# OTR.net
KiCad netlist of a schematic drawn in EAGLE
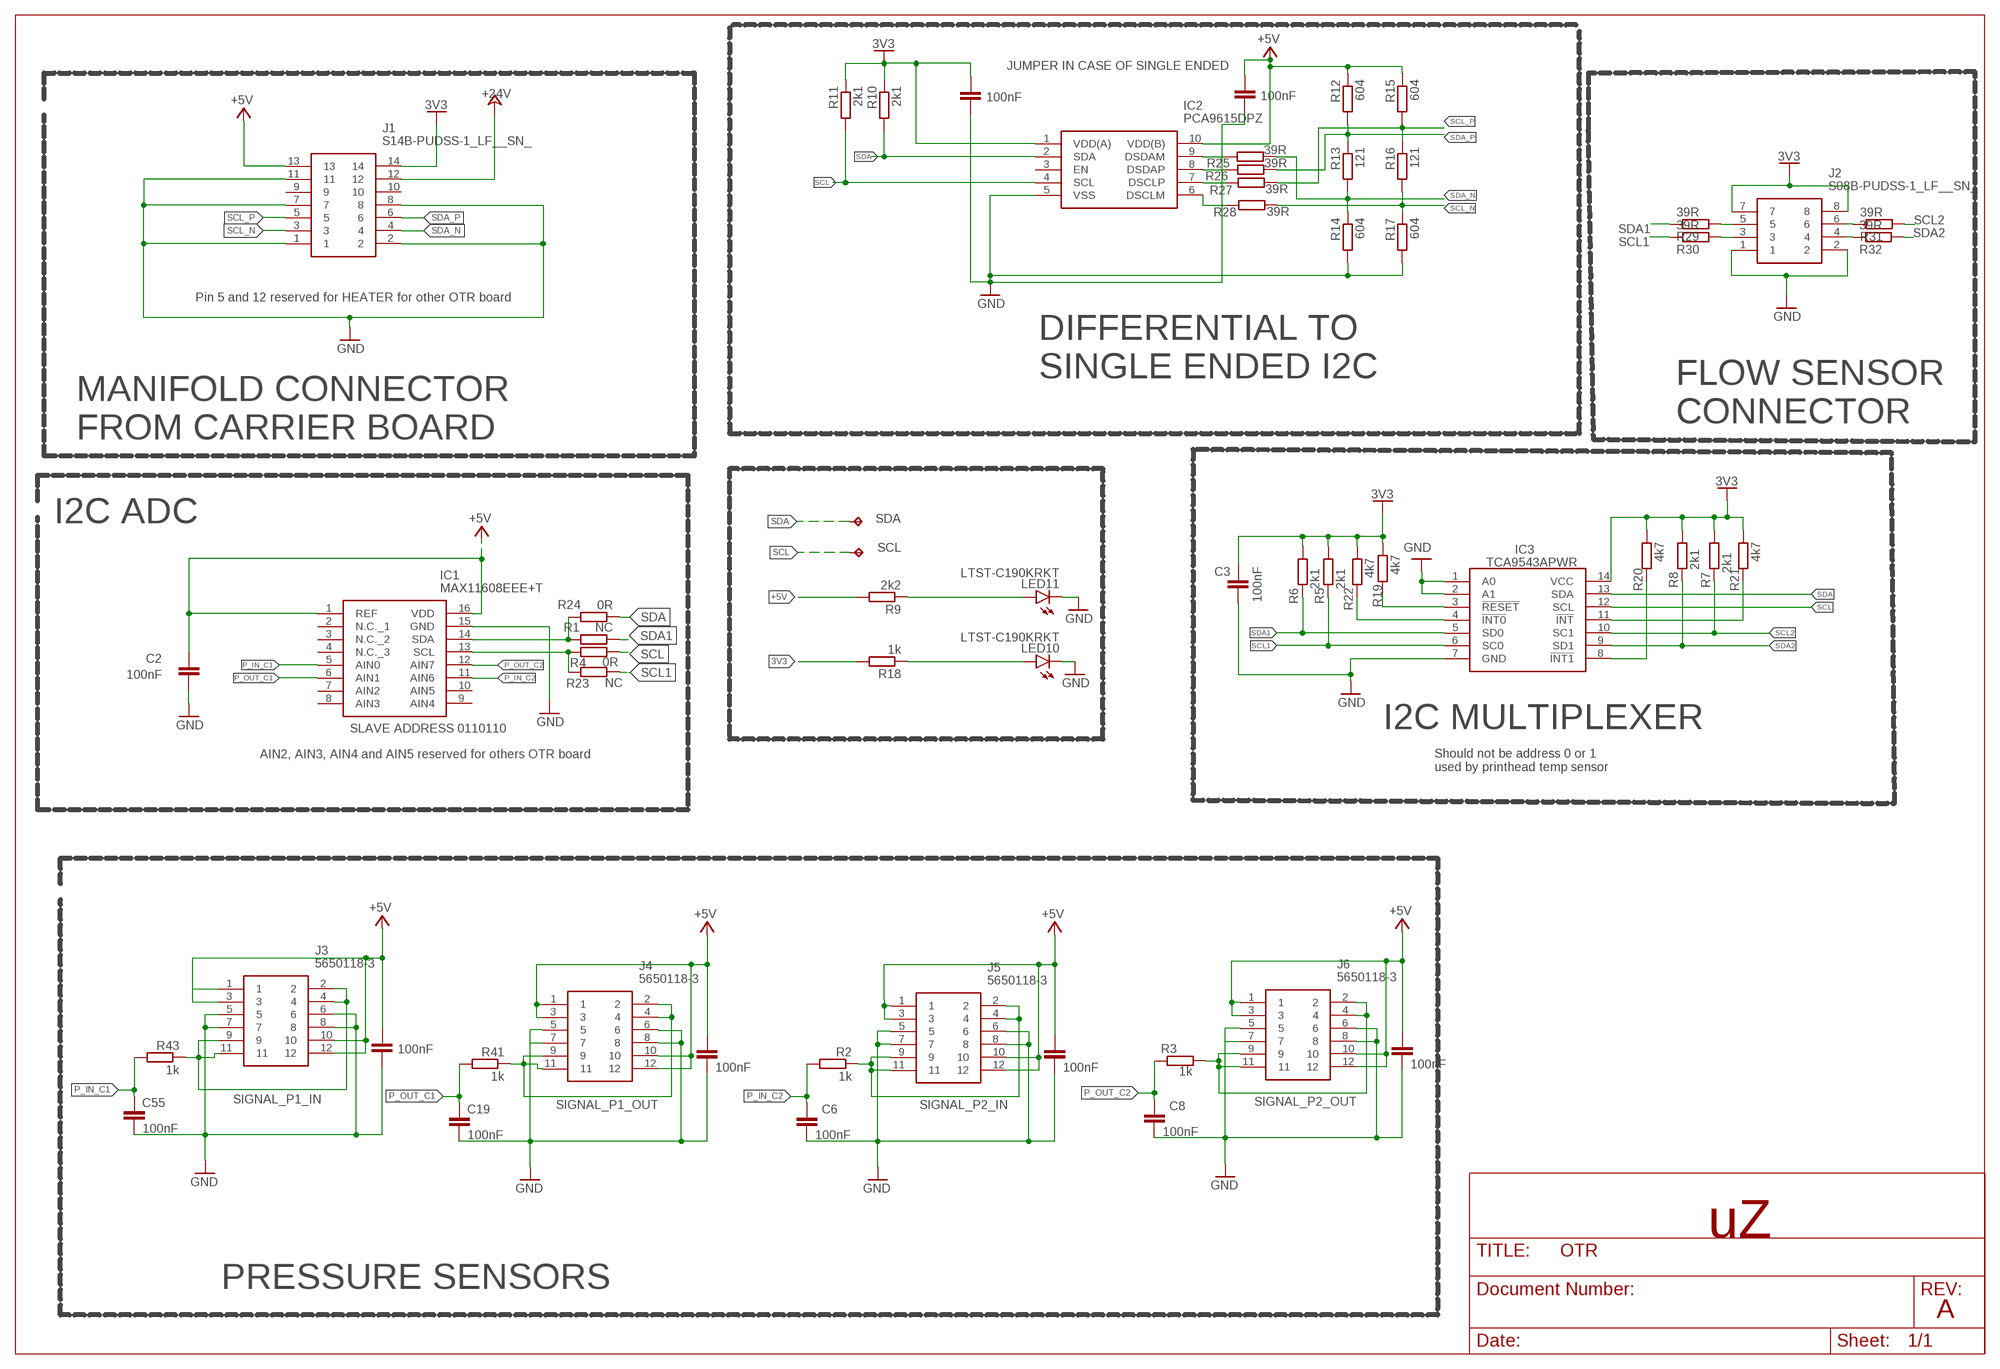
[diagram p0: schematic, sheet 1]

(export (version "E")
  (design (tool "Eeschema 10.0.6"))
  (components
    (comp (ref "C1")
      (value "100nF")
      (footprint "eagle-import:C0603")
      (libsource (lib "eagle-import") (part "C-EUC0603"))
    )
    (comp (ref "C2")
      (value "100nF")
      (footprint "eagle-import:C0603")
      (libsource (lib "eagle-import") (part "C-EUC0603"))
    )
    (comp (ref "C3")
      (value "100nF")
      (footprint "eagle-import:C0603")
      (libsource (lib "eagle-import") (part "C-EUC0603"))
    )
    (comp (ref "C4")
      (value "100nF")
      (footprint "eagle-import:C0603")
      (libsource (lib "eagle-import") (part "C-EUC0603"))
    )
    (comp (ref "C5")
      (value "100nF")
      (footprint "eagle-import:C0603")
      (libsource (lib "eagle-import") (part "C-EUC0603"))
    )
    (comp (ref "C6")
      (value "100nF")
      (footprint "eagle-import:C0603")
      (libsource (lib "eagle-import") (part "C-EUC0603"))
    )
    (comp (ref "C7")
      (value "100nF")
      (footprint "eagle-import:C0603")
      (libsource (lib "eagle-import") (part "C-EUC0603"))
    )
    (comp (ref "C8")
      (value "100nF")
      (footprint "eagle-import:C0603")
      (libsource (lib "eagle-import") (part "C-EUC0603"))
    )
    (comp (ref "C16")
      (value "100nF")
      (footprint "eagle-import:C0603")
      (libsource (lib "eagle-import") (part "C-EUC0603"))
    )
    (comp (ref "C19")
      (value "100nF")
      (footprint "eagle-import:C0603")
      (libsource (lib "eagle-import") (part "C-EUC0603"))
    )
    (comp (ref "C24")
      (value "100nF")
      (footprint "eagle-import:C0603")
      (libsource (lib "eagle-import") (part "C-EUC0603"))
    )
    (comp (ref "C55")
      (value "100nF")
      (footprint "eagle-import:C0603")
      (libsource (lib "eagle-import") (part "C-EUC0603"))
    )
    (comp (ref "IC1")
      (value "MAX11608EEE+T")
      (footprint "eagle-import:SOP64P602X175-16N")
      (fields (field (name "MOUSER_PART_NUMBER") "700-MAX11608EEE+T"))
      (libsource (lib "eagle-import") (part "MAX11608EEE+T"))
    )
    (comp (ref "IC2")
      (value "PCA9615DPZ")
      (footprint "eagle-import:SOP50P490X110-10N")
      (fields (field (name "MOUSER_PART_NUMBER") "771-PCA9615DPZ"))
      (libsource (lib "eagle-import") (part "PCA9615DPZ"))
    )
    (comp (ref "IC3")
      (value "TCA9543APWR")
      (footprint "eagle-import:SOP65P640X120-14N")
      (fields (field (name "MOUSER_PART_NUMBER") "595-TCA9543APWR"))
      (libsource (lib "eagle-import") (part "TCA9543APWR"))
    )
    (comp (ref "J1")
      (value "S14B-PUDSS-1_LF__SN_")
      (footprint "eagle-import:S14BPUDSS1LFSN")
      (fields (field (name "MANUFACTURER_PART_NUMBER") "S14B-PUDSS-1(LF)(SN)"))
      (libsource (lib "eagle-import") (part "S14B-PUDSS-1_LF__SN_"))
    )
    (comp (ref "J2")
      (value "S08B-PUDSS-1_LF__SN_")
      (footprint "eagle-import:S08B-PUDSS-1_LF__SN_")
      (fields (field (name "MANUFACTURER_PART_NUMBER") "S14B-PUDSS-1(LF)(SN)"))
      (libsource (lib "eagle-import") (part "S08B-PUDSS-1_LF__SN_"))
    )
    (comp (ref "J3")
      (value "5650118-3")
      (footprint "eagle-import:56501183")
      (fields (field (name "MOUSER_PART_NUMBER") "571-5650118-3"))
      (libsource (lib "eagle-import") (part "5650118-3"))
    )
    (comp (ref "J4")
      (value "5650118-3")
      (footprint "eagle-import:56501183")
      (fields (field (name "MOUSER_PART_NUMBER") "571-5650118-3"))
      (libsource (lib "eagle-import") (part "5650118-3"))
    )
    (comp (ref "J5")
      (value "5650118-3")
      (footprint "eagle-import:56501183")
      (fields (field (name "MOUSER_PART_NUMBER") "571-5650118-3"))
      (libsource (lib "eagle-import") (part "5650118-3"))
    )
    (comp (ref "J6")
      (value "5650118-3")
      (footprint "eagle-import:56501183")
      (fields (field (name "MOUSER_PART_NUMBER") "571-5650118-3"))
      (libsource (lib "eagle-import") (part "5650118-3"))
    )
    (comp (ref "LED10")
      (value "LTST-C190KRKT")
      (footprint "eagle-import:CHIPLED_0603")
      (libsource (lib "eagle-import") (part "LEDCHIPLED_0603"))
    )
    (comp (ref "LED11")
      (value "LTST-C190KRKT")
      (footprint "eagle-import:CHIPLED_0603")
      (libsource (lib "eagle-import") (part "LEDCHIPLED_0603"))
    )
    (comp (ref "R1")
      (value "NC")
      (footprint "eagle-import:R0603")
      (libsource (lib "eagle-import") (part "R-EU_R0603"))
    )
    (comp (ref "R2")
      (value "1k")
      (footprint "eagle-import:R0603")
      (libsource (lib "eagle-import") (part "R-EU_R0603"))
    )
    (comp (ref "R3")
      (value "1k")
      (footprint "eagle-import:R0603")
      (libsource (lib "eagle-import") (part "R-EU_R0603"))
    )
    (comp (ref "R4")
      (value "0R")
      (footprint "eagle-import:R0603")
      (libsource (lib "eagle-import") (part "R-EU_R0603"))
    )
    (comp (ref "R5")
      (value "2k1")
      (footprint "eagle-import:R0603")
      (libsource (lib "eagle-import") (part "R-EU_R0603"))
    )
    (comp (ref "R6")
      (value "2k1")
      (footprint "eagle-import:R0603")
      (libsource (lib "eagle-import") (part "R-EU_R0603"))
    )
    (comp (ref "R7")
      (value "2k1")
      (footprint "eagle-import:R0603")
      (libsource (lib "eagle-import") (part "R-EU_R0603"))
    )
    (comp (ref "R8")
      (value "2k1")
      (footprint "eagle-import:R0603")
      (libsource (lib "eagle-import") (part "R-EU_R0603"))
    )
    (comp (ref "R9")
      (value "2k2")
      (footprint "eagle-import:R0603")
      (libsource (lib "eagle-import") (part "R-EU_R0603"))
    )
    (comp (ref "R10")
      (value "2k1")
      (footprint "eagle-import:R0603")
      (libsource (lib "eagle-import") (part "R-EU_R0603"))
    )
    (comp (ref "R11")
      (value "2k1")
      (footprint "eagle-import:R0603")
      (libsource (lib "eagle-import") (part "R-EU_R0603"))
    )
    (comp (ref "R12")
      (value "604")
      (footprint "eagle-import:R0603")
      (libsource (lib "eagle-import") (part "R-EU_R0603"))
    )
    (comp (ref "R13")
      (value "121")
      (footprint "eagle-import:R0603")
      (libsource (lib "eagle-import") (part "R-EU_R0603"))
    )
    (comp (ref "R14")
      (value "604")
      (footprint "eagle-import:R0603")
      (libsource (lib "eagle-import") (part "R-EU_R0603"))
    )
    (comp (ref "R15")
      (value "604")
      (footprint "eagle-import:R0603")
      (libsource (lib "eagle-import") (part "R-EU_R0603"))
    )
    (comp (ref "R16")
      (value "121")
      (footprint "eagle-import:R0603")
      (libsource (lib "eagle-import") (part "R-EU_R0603"))
    )
    (comp (ref "R17")
      (value "604")
      (footprint "eagle-import:R0603")
      (libsource (lib "eagle-import") (part "R-EU_R0603"))
    )
    (comp (ref "R18")
      (value "1k")
      (footprint "eagle-import:R0603")
      (libsource (lib "eagle-import") (part "R-EU_R0603"))
    )
    (comp (ref "R19")
      (value "4k7")
      (footprint "eagle-import:R0603")
      (libsource (lib "eagle-import") (part "R-EU_R0603"))
    )
    (comp (ref "R20")
      (value "4k7")
      (footprint "eagle-import:R0603")
      (libsource (lib "eagle-import") (part "R-EU_R0603"))
    )
    (comp (ref "R21")
      (value "4k7")
      (footprint "eagle-import:R0603")
      (libsource (lib "eagle-import") (part "R-EU_R0603"))
    )
    (comp (ref "R22")
      (value "4k7")
      (footprint "eagle-import:R0603")
      (libsource (lib "eagle-import") (part "R-EU_R0603"))
    )
    (comp (ref "R23")
      (value "NC")
      (footprint "eagle-import:R0603")
      (libsource (lib "eagle-import") (part "R-EU_R0603"))
    )
    (comp (ref "R24")
      (value "0R")
      (footprint "eagle-import:R0603")
      (libsource (lib "eagle-import") (part "R-EU_R0603"))
    )
    (comp (ref "R25")
      (value "39R")
      (footprint "eagle-import:R0603")
      (libsource (lib "eagle-import") (part "R-EU_R0603"))
    )
    (comp (ref "R26")
      (value "39R")
      (footprint "eagle-import:R0603")
      (libsource (lib "eagle-import") (part "R-EU_R0603"))
    )
    (comp (ref "R27")
      (value "39R")
      (footprint "eagle-import:R0603")
      (libsource (lib "eagle-import") (part "R-EU_R0603"))
    )
    (comp (ref "R28")
      (value "39R")
      (footprint "eagle-import:R0603")
      (libsource (lib "eagle-import") (part "R-EU_R0603"))
    )
    (comp (ref "R29")
      (value "39R")
      (footprint "eagle-import:R0603")
      (libsource (lib "eagle-import") (part "R-EU_R0603"))
    )
    (comp (ref "R30")
      (value "39R")
      (footprint "eagle-import:R0603")
      (libsource (lib "eagle-import") (part "R-EU_R0603"))
    )
    (comp (ref "R31")
      (value "39R")
      (footprint "eagle-import:R0603")
      (libsource (lib "eagle-import") (part "R-EU_R0603"))
    )
    (comp (ref "R32")
      (value "39R")
      (footprint "eagle-import:R0603")
      (libsource (lib "eagle-import") (part "R-EU_R0603"))
    )
    (comp (ref "R41")
      (value "1k")
      (footprint "eagle-import:R0603")
      (libsource (lib "eagle-import") (part "R-EU_R0603"))
    )
    (comp (ref "R43")
      (value "1k")
      (footprint "eagle-import:R0603")
      (libsource (lib "eagle-import") (part "R-EU_R0603"))
    )
    (comp (ref "SCL")
      (value "TEST_POINT")
      (footprint "eagle-import:TEST_POINT")
      (libsource (lib "eagle-import") (part "TEST_POINT"))
    )
    (comp (ref "SDA")
      (value "TEST_POINT")
      (footprint "eagle-import:TEST_POINT")
      (libsource (lib "eagle-import") (part "TEST_POINT"))
    )
  )
  (nets
    (net (code "1") (name "+5V") (class "Default")
      (node (ref "C16") (pin "1") (pinfunction "1_1") (pintype "passive"))
      (node (ref "C2") (pin "1") (pinfunction "1_1") (pintype "passive"))
      (node (ref "C24") (pin "1") (pinfunction "1_1") (pintype "passive"))
      (node (ref "C4") (pin "1") (pinfunction "1_1") (pintype "passive"))
      (node (ref "C5") (pin "1") (pinfunction "1_1") (pintype "passive"))
      (node (ref "C7") (pin "1") (pinfunction "1_1") (pintype "passive"))
      (node (ref "IC1") (pin "1") (pinfunction "REF_1") (pintype "bidirectional"))
      (node (ref "IC1") (pin "16") (pinfunction "VDD_16") (pintype "bidirectional"))
      (node (ref "IC2") (pin "10") (pinfunction "VDD(B)_10") (pintype "bidirectional"))
      (node (ref "J1") (pin "13") (pinfunction "13_13") (pintype "bidirectional"))
      (node (ref "J3") (pin "1") (pinfunction "1_1") (pintype "bidirectional"))
      (node (ref "J3") (pin "10") (pinfunction "10_10") (pintype "bidirectional"))
      (node (ref "J3") (pin "12") (pinfunction "12_12") (pintype "bidirectional"))
      (node (ref "J3") (pin "3") (pinfunction "3_3") (pintype "bidirectional"))
      (node (ref "J4") (pin "1") (pinfunction "1_1") (pintype "bidirectional"))
      (node (ref "J4") (pin "10") (pinfunction "10_10") (pintype "bidirectional"))
      (node (ref "J4") (pin "12") (pinfunction "12_12") (pintype "bidirectional"))
      (node (ref "J4") (pin "3") (pinfunction "3_3") (pintype "bidirectional"))
      (node (ref "J5") (pin "1") (pinfunction "1_1") (pintype "bidirectional"))
      (node (ref "J5") (pin "10") (pinfunction "10_10") (pintype "bidirectional"))
      (node (ref "J5") (pin "12") (pinfunction "12_12") (pintype "bidirectional"))
      (node (ref "J5") (pin "3") (pinfunction "3_3") (pintype "bidirectional"))
      (node (ref "J6") (pin "1") (pinfunction "1_1") (pintype "bidirectional"))
      (node (ref "J6") (pin "10") (pinfunction "10_10") (pintype "bidirectional"))
      (node (ref "J6") (pin "12") (pinfunction "12_12") (pintype "bidirectional"))
      (node (ref "J6") (pin "3") (pinfunction "3_3") (pintype "bidirectional"))
      (node (ref "R12") (pin "1") (pinfunction "1_1") (pintype "passive"))
      (node (ref "R15") (pin "1") (pinfunction "1_1") (pintype "passive"))
      (node (ref "R9") (pin "2") (pinfunction "2_2") (pintype "passive"))
    )
    (net (code "2") (name "+24V") (class "Default")
      (node (ref "J1") (pin "12") (pinfunction "12_12") (pintype "bidirectional"))
    )
    (net (code "3") (name "/SIGNAL_P1_IN") (class "Default")
      (node (ref "J3") (pin "11") (pinfunction "11_11") (pintype "bidirectional"))
      (node (ref "J3") (pin "2") (pinfunction "2_2") (pintype "bidirectional"))
      (node (ref "J3") (pin "4") (pinfunction "4_4") (pintype "bidirectional"))
      (node (ref "J3") (pin "9") (pinfunction "9_9") (pintype "bidirectional"))
      (node (ref "R43") (pin "1") (pinfunction "1_1") (pintype "passive"))
    )
    (net (code "4") (name "/SIGNAL_P1_OUT") (class "Default")
      (node (ref "J4") (pin "11") (pinfunction "11_11") (pintype "bidirectional"))
      (node (ref "J4") (pin "2") (pinfunction "2_2") (pintype "bidirectional"))
      (node (ref "J4") (pin "4") (pinfunction "4_4") (pintype "bidirectional"))
      (node (ref "J4") (pin "9") (pinfunction "9_9") (pintype "bidirectional"))
      (node (ref "R41") (pin "1") (pinfunction "1_1") (pintype "passive"))
    )
    (net (code "5") (name "/SIGNAL_P2_IN") (class "Default")
      (node (ref "J5") (pin "11") (pinfunction "11_11") (pintype "bidirectional"))
      (node (ref "J5") (pin "2") (pinfunction "2_2") (pintype "bidirectional"))
      (node (ref "J5") (pin "4") (pinfunction "4_4") (pintype "bidirectional"))
      (node (ref "J5") (pin "9") (pinfunction "9_9") (pintype "bidirectional"))
      (node (ref "R2") (pin "1") (pinfunction "1_1") (pintype "passive"))
    )
    (net (code "6") (name "/SIGNAL_P2_OUT") (class "Default")
      (node (ref "J6") (pin "11") (pinfunction "11_11") (pintype "bidirectional"))
      (node (ref "J6") (pin "2") (pinfunction "2_2") (pintype "bidirectional"))
      (node (ref "J6") (pin "4") (pinfunction "4_4") (pintype "bidirectional"))
      (node (ref "J6") (pin "9") (pinfunction "9_9") (pintype "bidirectional"))
      (node (ref "R3") (pin "1") (pinfunction "1_1") (pintype "passive"))
    )
    (net (code "7") (name "3V3") (class "Default")
      (node (ref "C1") (pin "1") (pinfunction "1_1") (pintype "passive"))
      (node (ref "C3") (pin "2") (pinfunction "2_2") (pintype "passive"))
      (node (ref "IC2") (pin "1") (pinfunction "VDD(A)_1") (pintype "bidirectional"))
      (node (ref "IC3") (pin "14") (pinfunction "VCC_14") (pintype "bidirectional"))
      (node (ref "J1") (pin "14") (pinfunction "14_14") (pintype "bidirectional"))
      (node (ref "J2") (pin "7") (pinfunction "7_7") (pintype "bidirectional"))
      (node (ref "J2") (pin "8") (pinfunction "8_8") (pintype "bidirectional"))
      (node (ref "R10") (pin "1") (pinfunction "1_1") (pintype "passive"))
      (node (ref "R11") (pin "1") (pinfunction "1_1") (pintype "passive"))
      (node (ref "R18") (pin "2") (pinfunction "2_2") (pintype "passive"))
      (node (ref "R19") (pin "2") (pinfunction "2_2") (pintype "passive"))
      (node (ref "R20") (pin "2") (pinfunction "2_2") (pintype "passive"))
      (node (ref "R21") (pin "2") (pinfunction "2_2") (pintype "passive"))
      (node (ref "R22") (pin "2") (pinfunction "2_2") (pintype "passive"))
      (node (ref "R5") (pin "1") (pinfunction "1_1") (pintype "passive"))
      (node (ref "R6") (pin "1") (pinfunction "1_1") (pintype "passive"))
      (node (ref "R7") (pin "1") (pinfunction "1_1") (pintype "passive"))
      (node (ref "R8") (pin "1") (pinfunction "1_1") (pintype "passive"))
    )
    (net (code "8") (name "GND") (class "Default")
      (node (ref "C1") (pin "2") (pinfunction "2_2") (pintype "passive"))
      (node (ref "C16") (pin "2") (pinfunction "2_2") (pintype "passive"))
      (node (ref "C19") (pin "2") (pinfunction "2_2") (pintype "passive"))
      (node (ref "C2") (pin "2") (pinfunction "2_2") (pintype "passive"))
      (node (ref "C24") (pin "2") (pinfunction "2_2") (pintype "passive"))
      (node (ref "C3") (pin "1") (pinfunction "1_1") (pintype "passive"))
      (node (ref "C4") (pin "2") (pinfunction "2_2") (pintype "passive"))
      (node (ref "C5") (pin "2") (pinfunction "2_2") (pintype "passive"))
      (node (ref "C55") (pin "2") (pinfunction "2_2") (pintype "passive"))
      (node (ref "C6") (pin "2") (pinfunction "2_2") (pintype "passive"))
      (node (ref "C7") (pin "2") (pinfunction "2_2") (pintype "passive"))
      (node (ref "C8") (pin "2") (pinfunction "2_2") (pintype "passive"))
      (node (ref "IC1") (pin "15") (pinfunction "GND_15") (pintype "bidirectional"))
      (node (ref "IC2") (pin "5") (pinfunction "VSS_5") (pintype "bidirectional"))
      (node (ref "IC3") (pin "1") (pinfunction "A0_1") (pintype "bidirectional"))
      (node (ref "IC3") (pin "2") (pinfunction "A1_2") (pintype "bidirectional"))
      (node (ref "IC3") (pin "7") (pinfunction "GND_7") (pintype "bidirectional"))
      (node (ref "J1") (pin "1") (pinfunction "1_1") (pintype "bidirectional"))
      (node (ref "J1") (pin "11") (pinfunction "11_11") (pintype "bidirectional"))
      (node (ref "J1") (pin "2") (pinfunction "2_2") (pintype "bidirectional"))
      (node (ref "J1") (pin "7") (pinfunction "7_7") (pintype "bidirectional"))
      (node (ref "J1") (pin "8") (pinfunction "8_8") (pintype "bidirectional"))
      (node (ref "J2") (pin "1") (pinfunction "1_1") (pintype "bidirectional"))
      (node (ref "J2") (pin "2") (pinfunction "2_2") (pintype "bidirectional"))
      (node (ref "J3") (pin "5") (pinfunction "5_5") (pintype "bidirectional"))
      (node (ref "J3") (pin "6") (pinfunction "6_6") (pintype "bidirectional"))
      (node (ref "J3") (pin "7") (pinfunction "7_7") (pintype "bidirectional"))
      (node (ref "J3") (pin "8") (pinfunction "8_8") (pintype "bidirectional"))
      (node (ref "J4") (pin "5") (pinfunction "5_5") (pintype "bidirectional"))
      (node (ref "J4") (pin "6") (pinfunction "6_6") (pintype "bidirectional"))
      (node (ref "J4") (pin "7") (pinfunction "7_7") (pintype "bidirectional"))
      (node (ref "J4") (pin "8") (pinfunction "8_8") (pintype "bidirectional"))
      (node (ref "J5") (pin "5") (pinfunction "5_5") (pintype "bidirectional"))
      (node (ref "J5") (pin "6") (pinfunction "6_6") (pintype "bidirectional"))
      (node (ref "J5") (pin "7") (pinfunction "7_7") (pintype "bidirectional"))
      (node (ref "J5") (pin "8") (pinfunction "8_8") (pintype "bidirectional"))
      (node (ref "J6") (pin "5") (pinfunction "5_5") (pintype "bidirectional"))
      (node (ref "J6") (pin "6") (pinfunction "6_6") (pintype "bidirectional"))
      (node (ref "J6") (pin "7") (pinfunction "7_7") (pintype "bidirectional"))
      (node (ref "J6") (pin "8") (pinfunction "8_8") (pintype "bidirectional"))
      (node (ref "LED10") (pin "C") (pinfunction "C_C") (pintype "passive"))
      (node (ref "LED11") (pin "C") (pinfunction "C_C") (pintype "passive"))
      (node (ref "R14") (pin "2") (pinfunction "2_2") (pintype "passive"))
      (node (ref "R17") (pin "2") (pinfunction "2_2") (pintype "passive"))
    )
    (net (code "9") (name "Net-(IC1-SCL)") (class "Default")
      (node (ref "IC1") (pin "13") (pinfunction "SCL_13") (pintype "bidirectional"))
      (node (ref "R23") (pin "2") (pinfunction "2_2") (pintype "passive"))
      (node (ref "R4") (pin "2") (pinfunction "2_2") (pintype "passive"))
    )
    (net (code "10") (name "Net-(IC1-SDA)") (class "Default")
      (node (ref "IC1") (pin "14") (pinfunction "SDA_14") (pintype "bidirectional"))
      (node (ref "R1") (pin "2") (pinfunction "2_2") (pintype "passive"))
      (node (ref "R24") (pin "2") (pinfunction "2_2") (pintype "passive"))
    )
    (net (code "11") (name "Net-(IC2-DSCLM)") (class "Default")
      (node (ref "IC2") (pin "6") (pinfunction "DSCLM_6") (pintype "bidirectional"))
      (node (ref "R28") (pin "1") (pinfunction "1_1") (pintype "passive"))
    )
    (net (code "12") (name "Net-(IC2-DSCLP)") (class "Default")
      (node (ref "IC2") (pin "7") (pinfunction "DSCLP_7") (pintype "bidirectional"))
      (node (ref "R27") (pin "1") (pinfunction "1_1") (pintype "passive"))
    )
    (net (code "13") (name "Net-(IC2-DSDAM)") (class "Default")
      (node (ref "IC2") (pin "9") (pinfunction "DSDAM_9") (pintype "bidirectional"))
      (node (ref "R25") (pin "1") (pinfunction "1_1") (pintype "passive"))
    )
    (net (code "14") (name "Net-(IC2-DSDAP)") (class "Default")
      (node (ref "IC2") (pin "8") (pinfunction "DSDAP_8") (pintype "bidirectional"))
      (node (ref "R26") (pin "1") (pinfunction "1_1") (pintype "passive"))
    )
    (net (code "15") (name "Net-(IC3-~{INT0})") (class "Default")
      (node (ref "IC3") (pin "4") (pinfunction "~{INT0}_4") (pintype "bidirectional"))
      (node (ref "R22") (pin "1") (pinfunction "1_1") (pintype "passive"))
    )
    (net (code "16") (name "Net-(IC3-~{INT1})") (class "Default")
      (node (ref "IC3") (pin "8") (pinfunction "~{INT1}_8") (pintype "bidirectional"))
      (node (ref "R20") (pin "1") (pinfunction "1_1") (pintype "passive"))
    )
    (net (code "17") (name "Net-(IC3-~{INT})") (class "Default")
      (node (ref "IC3") (pin "11") (pinfunction "~{INT}_11") (pintype "bidirectional"))
      (node (ref "R21") (pin "1") (pinfunction "1_1") (pintype "passive"))
    )
    (net (code "18") (name "Net-(IC3-~{RESET})") (class "Default")
      (node (ref "IC3") (pin "3") (pinfunction "~{RESET}_3") (pintype "bidirectional"))
      (node (ref "R19") (pin "1") (pinfunction "1_1") (pintype "passive"))
    )
    (net (code "19") (name "Net-(J2-Pad3)") (class "Default")
      (node (ref "J2") (pin "3") (pinfunction "3_3") (pintype "bidirectional"))
      (node (ref "R30") (pin "2") (pinfunction "2_2") (pintype "passive"))
    )
    (net (code "20") (name "Net-(J2-Pad4)") (class "Default")
      (node (ref "J2") (pin "4") (pinfunction "4_4") (pintype "bidirectional"))
      (node (ref "R32") (pin "1") (pinfunction "1_1") (pintype "passive"))
    )
    (net (code "21") (name "Net-(J2-Pad5)") (class "Default")
      (node (ref "J2") (pin "5") (pinfunction "5_5") (pintype "bidirectional"))
      (node (ref "R29") (pin "2") (pinfunction "2_2") (pintype "passive"))
    )
    (net (code "22") (name "Net-(J2-Pad6)") (class "Default")
      (node (ref "J2") (pin "6") (pinfunction "6_6") (pintype "bidirectional"))
      (node (ref "R31") (pin "1") (pinfunction "1_1") (pintype "passive"))
    )
    (net (code "23") (name "Net-(LED10-PadA)") (class "Default")
      (node (ref "LED10") (pin "A") (pinfunction "A_A") (pintype "passive"))
      (node (ref "R18") (pin "1") (pinfunction "1_1") (pintype "passive"))
    )
    (net (code "24") (name "Net-(LED11-PadA)") (class "Default")
      (node (ref "LED11") (pin "A") (pinfunction "A_A") (pintype "passive"))
      (node (ref "R9") (pin "1") (pinfunction "1_1") (pintype "passive"))
    )
    (net (code "25") (name "P_IN_C1") (class "Default")
      (node (ref "C55") (pin "1") (pinfunction "1_1") (pintype "passive"))
      (node (ref "IC1") (pin "5") (pinfunction "AIN0_5") (pintype "bidirectional"))
      (node (ref "R43") (pin "2") (pinfunction "2_2") (pintype "passive"))
    )
    (net (code "26") (name "P_IN_C2") (class "Default")
      (node (ref "C6") (pin "1") (pinfunction "1_1") (pintype "passive"))
      (node (ref "IC1") (pin "11") (pinfunction "AIN6_11") (pintype "bidirectional"))
      (node (ref "R2") (pin "2") (pinfunction "2_2") (pintype "passive"))
    )
    (net (code "27") (name "P_OUT_C1") (class "Default")
      (node (ref "C19") (pin "1") (pinfunction "1_1") (pintype "passive"))
      (node (ref "IC1") (pin "6") (pinfunction "AIN1_6") (pintype "bidirectional"))
      (node (ref "R41") (pin "2") (pinfunction "2_2") (pintype "passive"))
    )
    (net (code "28") (name "P_OUT_C2") (class "Default")
      (node (ref "C8") (pin "1") (pinfunction "1_1") (pintype "passive"))
      (node (ref "IC1") (pin "12") (pinfunction "AIN7_12") (pintype "bidirectional"))
      (node (ref "R3") (pin "2") (pinfunction "2_2") (pintype "passive"))
    )
    (net (code "29") (name "SCL") (class "Default")
      (node (ref "IC2") (pin "4") (pinfunction "SCL_4") (pintype "bidirectional"))
      (node (ref "IC3") (pin "12") (pinfunction "SCL_12") (pintype "bidirectional"))
      (node (ref "R11") (pin "2") (pinfunction "2_2") (pintype "passive"))
      (node (ref "R4") (pin "1") (pinfunction "1_1") (pintype "passive"))
      (node (ref "SCL") (pin "P$1") (pinfunction "TP_P$1") (pintype "input"))
    )
    (net (code "30") (name "SCL1") (class "Default")
      (node (ref "IC3") (pin "6") (pinfunction "SC0_6") (pintype "bidirectional"))
      (node (ref "R23") (pin "1") (pinfunction "1_1") (pintype "passive"))
      (node (ref "R30") (pin "1") (pinfunction "1_1") (pintype "passive"))
      (node (ref "R5") (pin "2") (pinfunction "2_2") (pintype "passive"))
    )
    (net (code "31") (name "SCL2") (class "Default")
      (node (ref "IC3") (pin "10") (pinfunction "SC1_10") (pintype "bidirectional"))
      (node (ref "R31") (pin "2") (pinfunction "2_2") (pintype "passive"))
      (node (ref "R7") (pin "2") (pinfunction "2_2") (pintype "passive"))
    )
    (net (code "32") (name "SCL_N") (class "Default")
      (node (ref "J1") (pin "3") (pinfunction "3_3") (pintype "bidirectional"))
      (node (ref "R16") (pin "2") (pinfunction "2_2") (pintype "passive"))
      (node (ref "R17") (pin "1") (pinfunction "1_1") (pintype "passive"))
      (node (ref "R28") (pin "2") (pinfunction "2_2") (pintype "passive"))
    )
    (net (code "33") (name "SCL_P") (class "Default")
      (node (ref "J1") (pin "5") (pinfunction "5_5") (pintype "bidirectional"))
      (node (ref "R15") (pin "2") (pinfunction "2_2") (pintype "passive"))
      (node (ref "R16") (pin "1") (pinfunction "1_1") (pintype "passive"))
      (node (ref "R27") (pin "2") (pinfunction "2_2") (pintype "passive"))
    )
    (net (code "34") (name "SDA") (class "Default")
      (node (ref "IC2") (pin "2") (pinfunction "SDA_2") (pintype "bidirectional"))
      (node (ref "IC3") (pin "13") (pinfunction "SDA_13") (pintype "bidirectional"))
      (node (ref "R10") (pin "2") (pinfunction "2_2") (pintype "passive"))
      (node (ref "R24") (pin "1") (pinfunction "1_1") (pintype "passive"))
      (node (ref "SDA") (pin "P$1") (pinfunction "TP_P$1") (pintype "input"))
    )
    (net (code "35") (name "SDA1") (class "Default")
      (node (ref "IC3") (pin "5") (pinfunction "SD0_5") (pintype "bidirectional"))
      (node (ref "R1") (pin "1") (pinfunction "1_1") (pintype "passive"))
      (node (ref "R29") (pin "1") (pinfunction "1_1") (pintype "passive"))
      (node (ref "R6") (pin "2") (pinfunction "2_2") (pintype "passive"))
    )
    (net (code "36") (name "SDA2") (class "Default")
      (node (ref "IC3") (pin "9") (pinfunction "SD1_9") (pintype "bidirectional"))
      (node (ref "R32") (pin "2") (pinfunction "2_2") (pintype "passive"))
      (node (ref "R8") (pin "2") (pinfunction "2_2") (pintype "passive"))
    )
    (net (code "37") (name "SDA_N") (class "Default")
      (node (ref "J1") (pin "4") (pinfunction "4_4") (pintype "bidirectional"))
      (node (ref "R13") (pin "2") (pinfunction "2_2") (pintype "passive"))
      (node (ref "R14") (pin "1") (pinfunction "1_1") (pintype "passive"))
      (node (ref "R25") (pin "2") (pinfunction "2_2") (pintype "passive"))
    )
    (net (code "38") (name "SDA_P") (class "Default")
      (node (ref "J1") (pin "6") (pinfunction "6_6") (pintype "bidirectional"))
      (node (ref "R12") (pin "2") (pinfunction "2_2") (pintype "passive"))
      (node (ref "R13") (pin "1") (pinfunction "1_1") (pintype "passive"))
      (node (ref "R26") (pin "2") (pinfunction "2_2") (pintype "passive"))
    )
    (net (code "39") (name "unconnected-(IC1-AIN2-Pad7)") (class "Default")
      (node (ref "IC1") (pin "7") (pinfunction "AIN2_7") (pintype "bidirectional"))
    )
    (net (code "40") (name "unconnected-(IC1-AIN3-Pad8)") (class "Default")
      (node (ref "IC1") (pin "8") (pinfunction "AIN3_8") (pintype "bidirectional"))
    )
    (net (code "41") (name "unconnected-(IC1-AIN4-Pad9)") (class "Default")
      (node (ref "IC1") (pin "9") (pinfunction "AIN4_9") (pintype "bidirectional"))
    )
    (net (code "42") (name "unconnected-(IC1-AIN5-Pad10)") (class "Default")
      (node (ref "IC1") (pin "10") (pinfunction "AIN5_10") (pintype "bidirectional"))
    )
    (net (code "43") (name "unconnected-(IC1-N.C._1-Pad2)") (class "Default")
      (node (ref "IC1") (pin "2") (pinfunction "N.C._1_2") (pintype "bidirectional"))
    )
    (net (code "44") (name "unconnected-(IC1-N.C._2-Pad3)") (class "Default")
      (node (ref "IC1") (pin "3") (pinfunction "N.C._2_3") (pintype "bidirectional"))
    )
    (net (code "45") (name "unconnected-(IC1-N.C._3-Pad4)") (class "Default")
      (node (ref "IC1") (pin "4") (pinfunction "N.C._3_4") (pintype "bidirectional"))
    )
    (net (code "46") (name "unconnected-(IC2-EN-Pad3)") (class "Default")
      (node (ref "IC2") (pin "3") (pinfunction "EN_3") (pintype "bidirectional"))
    )
    (net (code "47") (name "unconnected-(J1-Pad9)") (class "Default")
      (node (ref "J1") (pin "9") (pinfunction "9_9") (pintype "bidirectional"))
    )
    (net (code "48") (name "unconnected-(J1-Pad10)") (class "Default")
      (node (ref "J1") (pin "10") (pinfunction "10_10") (pintype "bidirectional"))
    )
  )
)
